# jlink_adapter_v0.net
KiCad netlist of a schematic drawn in Altium Designer
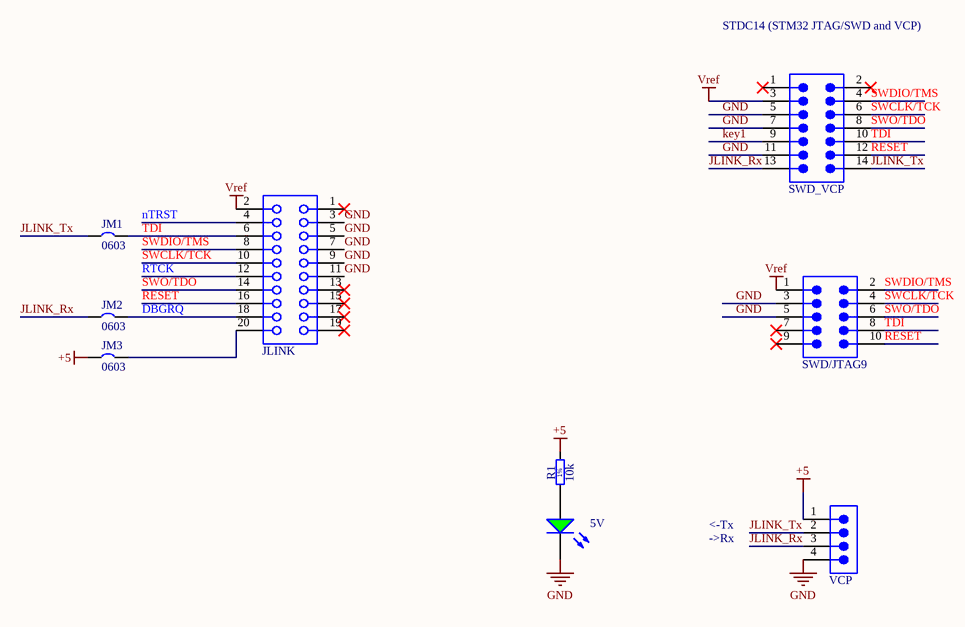
[diagram p0: jlink_adapter_v0.SchDoc]

(export (version "E")
  (design (tool "Eeschema 10.0.6"))
  (components
    (comp (ref "5V")
      (value "~")
      (footprint "LED0603")
      (description "LED green 0603")
      (fields (field (name "DRAWN BY") "P. Kawula"))
      (libsource (lib "diodes") (part "LED_G_0603"))
    )
    (comp (ref "JLINK")
      (value "613020243121")
      (footprint "613020243121")
      (description "WR-PHD Socket Header, THT, Angled, pitch 2.54mm, 2 Row, 20P")
      (fields (field (name "MANUFACTURER") "Wurth Elektronik"))
      (libsource (lib "Altium_WR-PHD (rev22b)") (part "613020243121"))
    )
    (comp (ref "JM1")
      (value "~")
      (footprint "NT0603_10")
      (description "Jumper")
      (fields
        (field (name "TOLERANCE") "5%")
        (field (name "PACKAGEREFERENCE") "0603")
        (field (name "DRAWN BY") "P. Kawula")
        (field (name "CHECKED BY") "*")
      )
      (libsource (lib "miscellaneous") (part "JM_0603"))
    )
    (comp (ref "JM2")
      (value "~")
      (footprint "NT0603_10")
      (description "Jumper")
      (fields
        (field (name "TOLERANCE") "5%")
        (field (name "PACKAGEREFERENCE") "0603")
        (field (name "DRAWN BY") "P. Kawula")
        (field (name "CHECKED BY") "*")
      )
      (libsource (lib "miscellaneous") (part "JM_0603"))
    )
    (comp (ref "JM3")
      (value "~")
      (footprint "NT0603_10")
      (description "Jumper")
      (fields
        (field (name "TOLERANCE") "5%")
        (field (name "PACKAGEREFERENCE") "0603")
        (field (name "DRAWN BY") "P. Kawula")
        (field (name "CHECKED BY") "*")
      )
      (libsource (lib "miscellaneous") (part "JM_0603"))
    )
    (comp (ref "R1")
      (value "10k")
      (footprint "RESC1608X55N")
      (description "Resistor - 1%")
      (fields
        (field (name "PART NUMBER") "R0603_10k_1%_0.1W_100ppm_VISHAY_CRCW060310K0FKEA")
        (field (name "POWER") "0.1W")
        (field (name "AUTHOR") "P. Kawula")
      )
      (libsource (lib "Resistors SMD") (part "R0603_10k_1%_0.1W_100ppm_VISHAY_CRCW060310K0FKEA"))
    )
    (comp (ref "SWD/JTAG9")
      (value "62701020621")
      (footprint "62701020621")
      (description "WR-BHD Male Box Header, SMT Straight, pitch 1.27mm, 2 Row, 10 pin")
      (fields (field (name "MANUFACTURER") "Wurth Elektronik"))
      (libsource (lib "Altium_WR-BHD (rev22c)") (part "62701020621"))
    )
    (comp (ref "SWD_VCP")
      (value "62731420621")
      (footprint "62731420621")
      (description "WR-BHD Male Box Header, SMT Straight, pitch 1.27mm, 2 Row, 14 pin")
      (fields (field (name "MANUFACTURER") "Wurth Elektronik"))
      (libsource (lib "Altium_WR-BHD (rev22c)") (part "62731420621"))
    )
    (comp (ref "VCP")
      (value "61300411121")
      (footprint "61300411121")
      (description "WR-PHD Pin Header, THT, Vertical, pitch 2.54mm, 1 Row, 4P")
      (fields (field (name "MANUFACTURER") "Wurth Elektronik"))
      (libsource (lib "Altium_WR-PHD (rev22b)") (part "61300411121"))
    )
  )
  (nets
    (net (code "1") (name "+5") (class "Default")
      (node (ref "JM3") (pin "1") (pinfunction "1_1") (pintype "passive"))
      (node (ref "R1") (pin "2") (pinfunction "2_2") (pintype "passive"))
      (node (ref "VCP") (pin "1") (pinfunction "1_1") (pintype "passive"))
    )
    (net (code "2") (name "/DBGRQ") (class "Default")
      (node (ref "JLINK") (pin "18") (pinfunction "18_18") (pintype "passive"))
      (node (ref "JM2") (pin "2") (pinfunction "2_2") (pintype "passive"))
    )
    (net (code "3") (name "/JLINK_Rx") (class "Default")
      (node (ref "JM2") (pin "1") (pinfunction "1_1") (pintype "passive"))
      (node (ref "SWD_VCP") (pin "13") (pinfunction "13_13") (pintype "passive"))
      (node (ref "VCP") (pin "3") (pinfunction "3_3") (pintype "passive"))
    )
    (net (code "4") (name "/JLINK_Tx") (class "Default")
      (node (ref "JM1") (pin "1") (pinfunction "1_1") (pintype "passive"))
      (node (ref "SWD_VCP") (pin "14") (pinfunction "14_14") (pintype "passive"))
      (node (ref "VCP") (pin "2") (pinfunction "2_2") (pintype "passive"))
    )
    (net (code "5") (name "/RESET") (class "Default")
      (node (ref "JLINK") (pin "16") (pinfunction "16_16") (pintype "passive"))
      (node (ref "SWD/JTAG9") (pin "10") (pinfunction "10_10") (pintype "passive"))
      (node (ref "SWD_VCP") (pin "12") (pinfunction "12_12") (pintype "passive"))
    )
    (net (code "6") (name "/RTCK") (class "Default")
      (node (ref "JLINK") (pin "12") (pinfunction "12_12") (pintype "passive"))
    )
    (net (code "7") (name "/SWCLK{slash}TCK") (class "Default")
      (node (ref "JLINK") (pin "10") (pinfunction "10_10") (pintype "passive"))
      (node (ref "SWD/JTAG9") (pin "4") (pinfunction "4_4") (pintype "passive"))
      (node (ref "SWD_VCP") (pin "6") (pinfunction "6_6") (pintype "passive"))
    )
    (net (code "8") (name "/SWDIO{slash}TMS") (class "Default")
      (node (ref "JLINK") (pin "8") (pinfunction "8_8") (pintype "passive"))
      (node (ref "SWD/JTAG9") (pin "2") (pinfunction "2_2") (pintype "passive"))
      (node (ref "SWD_VCP") (pin "4") (pinfunction "4_4") (pintype "passive"))
    )
    (net (code "9") (name "/SWO{slash}TDO") (class "Default")
      (node (ref "JLINK") (pin "14") (pinfunction "14_14") (pintype "passive"))
      (node (ref "SWD/JTAG9") (pin "6") (pinfunction "6_6") (pintype "passive"))
      (node (ref "SWD_VCP") (pin "8") (pinfunction "8_8") (pintype "passive"))
    )
    (net (code "10") (name "/TDI") (class "Default")
      (node (ref "JLINK") (pin "6") (pinfunction "6_6") (pintype "passive"))
      (node (ref "JM1") (pin "2") (pinfunction "2_2") (pintype "passive"))
      (node (ref "SWD/JTAG9") (pin "8") (pinfunction "8_8") (pintype "passive"))
      (node (ref "SWD_VCP") (pin "10") (pinfunction "10_10") (pintype "passive"))
    )
    (net (code "11") (name "/key1") (class "Default")
      (node (ref "SWD_VCP") (pin "9") (pinfunction "9_9") (pintype "passive"))
    )
    (net (code "12") (name "/nTRST") (class "Default")
      (node (ref "JLINK") (pin "4") (pinfunction "4_4") (pintype "passive"))
    )
    (net (code "13") (name "GND") (class "Default")
      (node (ref "5V") (pin "1") (pinfunction "K_1") (pintype "passive"))
      (node (ref "JLINK") (pin "11") (pinfunction "11_11") (pintype "passive"))
      (node (ref "JLINK") (pin "3") (pinfunction "3_3") (pintype "passive"))
      (node (ref "JLINK") (pin "5") (pinfunction "5_5") (pintype "passive"))
      (node (ref "JLINK") (pin "7") (pinfunction "7_7") (pintype "passive"))
      (node (ref "JLINK") (pin "9") (pinfunction "9_9") (pintype "passive"))
      (node (ref "SWD/JTAG9") (pin "3") (pinfunction "3_3") (pintype "passive"))
      (node (ref "SWD/JTAG9") (pin "5") (pinfunction "5_5") (pintype "passive"))
      (node (ref "SWD_VCP") (pin "11") (pinfunction "11_11") (pintype "passive"))
      (node (ref "SWD_VCP") (pin "5") (pinfunction "5_5") (pintype "passive"))
      (node (ref "SWD_VCP") (pin "7") (pinfunction "7_7") (pintype "passive"))
      (node (ref "VCP") (pin "4") (pinfunction "4_4") (pintype "passive"))
    )
    (net (code "14") (name "Net-(5V-A)") (class "Default")
      (node (ref "5V") (pin "2") (pinfunction "A_2") (pintype "passive"))
      (node (ref "R1") (pin "1") (pinfunction "1_1") (pintype "passive"))
    )
    (net (code "15") (name "Net-(JLINK-Pad20)") (class "Default")
      (node (ref "JLINK") (pin "20") (pinfunction "20_20") (pintype "passive"))
      (node (ref "JM3") (pin "2") (pinfunction "2_2") (pintype "passive"))
    )
    (net (code "16") (name "Vref") (class "Default")
      (node (ref "JLINK") (pin "2") (pinfunction "2_2") (pintype "passive"))
      (node (ref "SWD/JTAG9") (pin "1") (pinfunction "1_1") (pintype "passive"))
      (node (ref "SWD_VCP") (pin "3") (pinfunction "3_3") (pintype "passive"))
    )
    (net (code "17") (name "unconnected-(JLINK-Pad1)") (class "Default")
      (node (ref "JLINK") (pin "1") (pinfunction "1_1") (pintype "passive+no_connect"))
    )
    (net (code "18") (name "unconnected-(JLINK-Pad13)") (class "Default")
      (node (ref "JLINK") (pin "13") (pinfunction "13_13") (pintype "passive+no_connect"))
    )
    (net (code "19") (name "unconnected-(JLINK-Pad15)") (class "Default")
      (node (ref "JLINK") (pin "15") (pinfunction "15_15") (pintype "passive+no_connect"))
    )
    (net (code "20") (name "unconnected-(JLINK-Pad17)") (class "Default")
      (node (ref "JLINK") (pin "17") (pinfunction "17_17") (pintype "passive+no_connect"))
    )
    (net (code "21") (name "unconnected-(JLINK-Pad19)") (class "Default")
      (node (ref "JLINK") (pin "19") (pinfunction "19_19") (pintype "passive+no_connect"))
    )
    (net (code "22") (name "unconnected-(SWD/JTAG9-Pad7)") (class "Default")
      (node (ref "SWD/JTAG9") (pin "7") (pinfunction "7_7") (pintype "passive+no_connect"))
    )
    (net (code "23") (name "unconnected-(SWD/JTAG9-Pad9)") (class "Default")
      (node (ref "SWD/JTAG9") (pin "9") (pinfunction "9_9") (pintype "passive+no_connect"))
    )
    (net (code "24") (name "unconnected-(SWD_VCP-Pad1)") (class "Default")
      (node (ref "SWD_VCP") (pin "1") (pinfunction "1_1") (pintype "passive+no_connect"))
    )
    (net (code "25") (name "unconnected-(SWD_VCP-Pad2)") (class "Default")
      (node (ref "SWD_VCP") (pin "2") (pinfunction "2_2") (pintype "passive+no_connect"))
    )
  )
)
